# ESP8266.net
KiCad netlist of a schematic drawn in Altium Designer
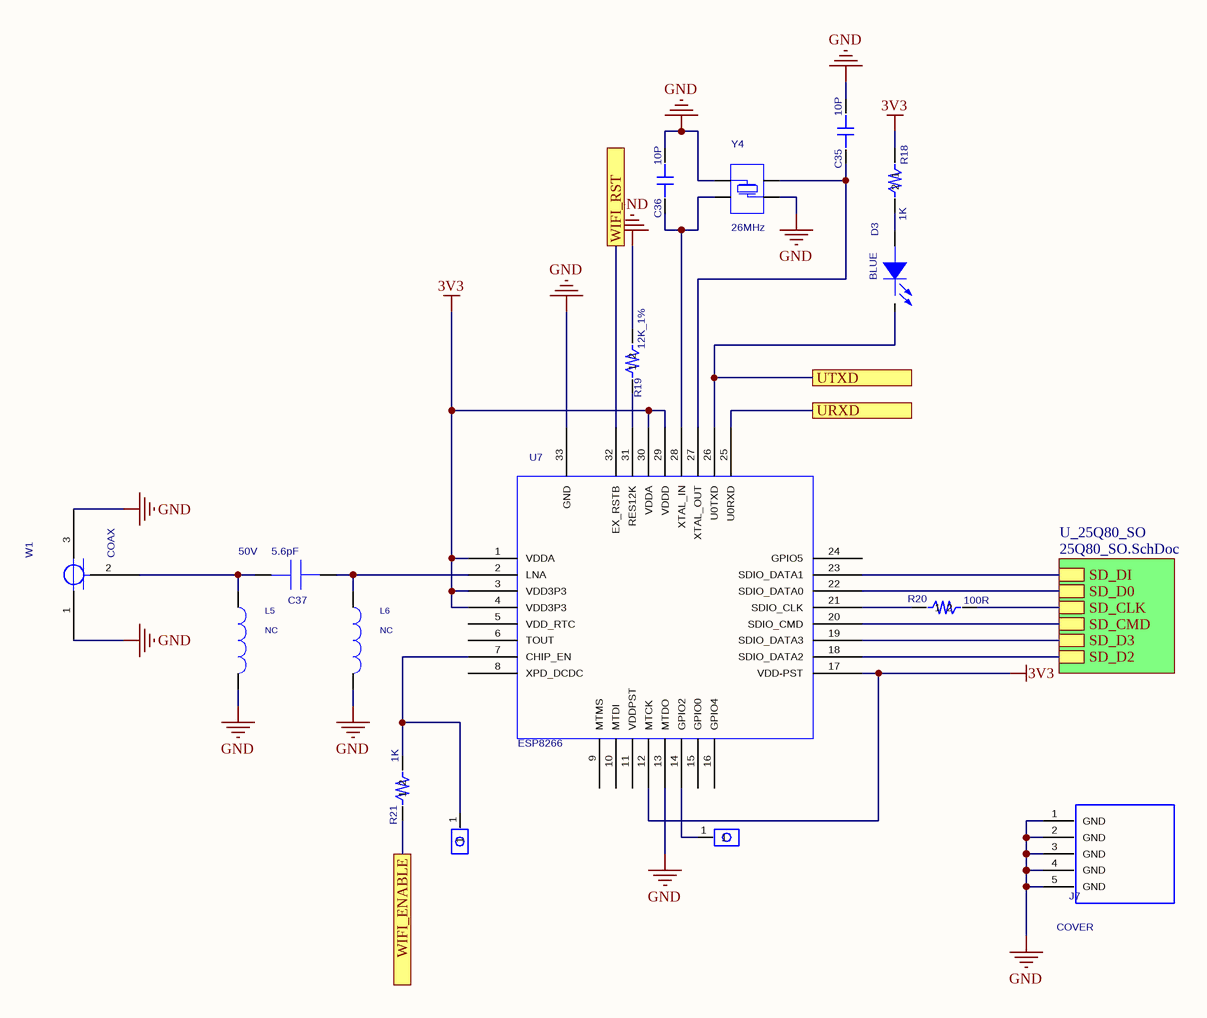
[diagram p0: ESP8266.SchDoc]

(export (version "E")
  (design (tool "Eeschema 10.0.6"))
  (components
    (comp (ref "C35")
      (value "10P")
      (footprint "RES_0603_FIRE")
      (description "0603")
      (fields (field (name "TOLERANCE") "+-5%") (field (name "Comment") "CAP_10P_0603_FIRE"))
      (libsource (lib "MINI-V3") (part "CAP_10P_0603_FIRE"))
    )
    (comp (ref "C36")
      (value "10P")
      (footprint "RES_0603_FIRE")
      (description "0603")
      (fields (field (name "TOLERANCE") "+-5%") (field (name "Comment") "CAP_10P_0603_FIRE"))
      (libsource (lib "MINI-V3") (part "CAP_10P_0603_FIRE"))
    )
    (comp (ref "C37")
      (value "5.6pF")
      (footprint "0603")
      (description "0603, X7R, 50V, 10%(K)")
      (fields (field (name "TOLERANCE") "±10%") (field (name "MFR") "Fenghua") (field (name "VOLTAGE") "50V"))
      (libsource (lib "MINI-V3") (part "CAP_NP"))
    )
    (comp (ref "D3")
      (value "BLUE")
      (footprint "LED_BLUE_0603_FIRE")
      (description "blue,0603")
      (fields (field (name "Comment") "LED_BLUE_0603_FIRE"))
      (libsource (lib "MINI-V3") (part "LED_BLUE_0603_FIRE"))
    )
    (comp (ref "J5") (value "1_DIP") (footprint "1_DIP") (libsource (lib "MINI-V3") (part "1_DIP")))
    (comp (ref "J6") (value "1_DIP") (footprint "1_DIP") (libsource (lib "MINI-V3") (part "1_DIP")))
    (comp (ref "J7") (value "COVER") (footprint "COVER1") (libsource (lib "MINI-V3") (part "COVER")))
    (comp (ref "L5")
      (value "NC")
      (footprint "0603")
      (description "1uH, 1.1R@245MHz, 245mA")
      (fields (field (name "TOLERANCE") "5%") (field (name "MFR") "TDK"))
      (libsource (lib "MINI-V3") (part "IND"))
    )
    (comp (ref "L6")
      (value "NC")
      (footprint "0603")
      (description "1uH, 1.1R@245MHz, 245mA")
      (fields (field (name "TOLERANCE") "5%") (field (name "MFR") "TDK"))
      (libsource (lib "MINI-V3") (part "IND"))
    )
    (comp (ref "R18")
      (value "1K")
      (footprint "RES_0603_FIRE")
      (description "0402")
      (fields (field (name "TOLERANCE") "+-5%") (field (name "Comment") "RES_1K_0603_FIRE"))
      (libsource (lib "MINI-V3") (part "RES_1K_0603_FIRE"))
    )
    (comp (ref "R19")
      (value "12K_1%")
      (footprint "RES_0603_FIRE")
      (description "0402")
      (fields (field (name "TOLERANCE") "+-1%") (field (name "Comment") "RES_12K_1%_0603_FIRE"))
      (libsource (lib "MINI-V3") (part "RES_12K_1%_0603_FIRE"))
    )
    (comp (ref "R20")
      (value "100R")
      (footprint "RES_0603_FIRE")
      (description "0402")
      (fields (field (name "TOLERANCE") "+-5%") (field (name "Comment") "RES_100R_0603_FIRE"))
      (libsource (lib "MINI-V3") (part "RES_100R_0603_FIRE"))
    )
    (comp (ref "R21")
      (value "1K")
      (footprint "RES_0603_FIRE")
      (description "0402")
      (fields (field (name "TOLERANCE") "+-5%") (field (name "Comment") "RES_1K_0603_FIRE"))
      (libsource (lib "MINI-V3") (part "RES_1K_0603_FIRE"))
    )
    (comp (ref "U7") (value "ESP8266") (footprint "QFN32_1") (libsource (lib "MINI-V3") (part "ESP8266")))
    (comp (ref "W1") (value "COAX") (footprint "UFL-3") (libsource (lib "MINI-V3") (part "COAX")))
    (comp (ref "Y4")
      (value "26MHz")
      (footprint "NX3225SA")
      (description "27.12MHz,SMD5032,-30 to 85℃")
      (fields (field (name "PART_NUMBER") "OS200008-01") (field (name "MFR_PART_NUMBER") "E5SB27_1200F20G13"))
      (libsource (lib "MINI-V3") (part "CRYSTAL5032"))
    )
  )
  (nets
    (net (code "1") (name "/SD_CLK") (class "Default")
      (node (ref "R20") (pin "2") (pinfunction "2_2") (pintype "passive"))
    )
    (net (code "2") (name "/SD_CMD") (class "Default")
      (node (ref "U7") (pin "20") (pinfunction "SDIO_CMD_20") (pintype "passive"))
    )
    (net (code "3") (name "/SD_D0") (class "Default")
      (node (ref "U7") (pin "22") (pinfunction "SDIO_DATA0_22") (pintype "passive"))
    )
    (net (code "4") (name "/SD_D2") (class "Default")
      (node (ref "U7") (pin "18") (pinfunction "SDIO_DATA2_18") (pintype "passive"))
    )
    (net (code "5") (name "/SD_D3") (class "Default")
      (node (ref "U7") (pin "19") (pinfunction "SDIO_DATA3_19") (pintype "passive"))
    )
    (net (code "6") (name "/SD_DI") (class "Default")
      (node (ref "U7") (pin "23") (pinfunction "SDIO_DATA1_23") (pintype "passive"))
    )
    (net (code "7") (name "/URXD") (class "Default")
      (node (ref "U7") (pin "25") (pinfunction "U0RXD_25") (pintype "passive"))
    )
    (net (code "8") (name "/UTXD") (class "Default")
      (node (ref "D3") (pin "K") (pinfunction "CATHODE_K") (pintype "passive"))
      (node (ref "U7") (pin "26") (pinfunction "U0TXD_26") (pintype "passive"))
    )
    (net (code "9") (name "/WIFI_ENABLE") (class "Default")
      (node (ref "R21") (pin "1") (pinfunction "1_1") (pintype "passive"))
    )
    (net (code "10") (name "/WIFI_RST") (class "Default")
      (node (ref "U7") (pin "32") (pinfunction "EX_RSTB_32") (pintype "passive"))
    )
    (net (code "11") (name "3V3") (class "Default")
      (node (ref "R18") (pin "1") (pinfunction "1_1") (pintype "passive"))
      (node (ref "U7") (pin "1") (pinfunction "VDDA_1") (pintype "passive"))
      (node (ref "U7") (pin "12") (pinfunction "MTCK_12") (pintype "passive"))
      (node (ref "U7") (pin "17") (pinfunction "VDD-PST_17") (pintype "passive"))
      (node (ref "U7") (pin "29") (pinfunction "VDDD_29") (pintype "passive"))
      (node (ref "U7") (pin "3") (pinfunction "VDD3P3_3") (pintype "passive"))
      (node (ref "U7") (pin "30") (pinfunction "VDDA_30") (pintype "passive"))
      (node (ref "U7") (pin "4") (pinfunction "VDD3P3_4") (pintype "passive"))
    )
    (net (code "12") (name "GND") (class "Default")
      (node (ref "C35") (pin "2") (pinfunction "2_2") (pintype "passive"))
      (node (ref "C36") (pin "2") (pinfunction "2_2") (pintype "passive"))
      (node (ref "J7") (pin "1") (pinfunction "GND_1") (pintype "passive"))
      (node (ref "J7") (pin "2") (pinfunction "GND_2") (pintype "passive"))
      (node (ref "J7") (pin "3") (pinfunction "GND_3") (pintype "passive"))
      (node (ref "J7") (pin "4") (pinfunction "GND_4") (pintype "passive"))
      (node (ref "J7") (pin "5") (pinfunction "GND_5") (pintype "passive"))
      (node (ref "L5") (pin "2") (pinfunction "2_2") (pintype "passive"))
      (node (ref "L6") (pin "2") (pinfunction "2_2") (pintype "passive"))
      (node (ref "R19") (pin "2") (pinfunction "2_2") (pintype "passive"))
      (node (ref "U7") (pin "13") (pinfunction "MTDO_13") (pintype "passive"))
      (node (ref "U7") (pin "33") (pinfunction "GND_33") (pintype "passive"))
      (node (ref "W1") (pin "1") (pinfunction "CENTER_1_1") (pintype "passive"))
      (node (ref "W1") (pin "3") (pinfunction "CENTER_2_3") (pintype "passive"))
      (node (ref "Y4") (pin "1") (pinfunction "1_1") (pintype "passive"))
      (node (ref "Y4") (pin "3") (pinfunction "3_3") (pintype "passive"))
    )
    (net (code "13") (name "Net-(D3-ANODE)") (class "Default")
      (node (ref "D3") (pin "A") (pinfunction "ANODE_A") (pintype "passive"))
      (node (ref "R18") (pin "2") (pinfunction "2_2") (pintype "passive"))
    )
    (net (code "14") (name "Net-(U7-CHIP_EN)") (class "Default")
      (node (ref "J6") (pin "1") (pinfunction "1_1") (pintype "passive"))
      (node (ref "R21") (pin "2") (pinfunction "2_2") (pintype "passive"))
      (node (ref "U7") (pin "7") (pinfunction "CHIP_EN_7") (pintype "passive"))
    )
    (net (code "15") (name "Net-(U7-GPIO2)") (class "Default")
      (node (ref "J5") (pin "1") (pinfunction "1_1") (pintype "passive"))
      (node (ref "U7") (pin "14") (pinfunction "GPIO2_14") (pintype "passive"))
    )
    (net (code "16") (name "Net-(U7-LNA)") (class "Default")
      (node (ref "C37") (pin "1") (pinfunction "1_1") (pintype "passive"))
      (node (ref "L6") (pin "1") (pinfunction "1_1") (pintype "passive"))
      (node (ref "U7") (pin "2") (pinfunction "LNA_2") (pintype "passive"))
    )
    (net (code "17") (name "Net-(U7-RES12K)") (class "Default")
      (node (ref "R19") (pin "1") (pinfunction "1_1") (pintype "passive"))
      (node (ref "U7") (pin "31") (pinfunction "RES12K_31") (pintype "passive"))
    )
    (net (code "18") (name "Net-(U7-SDIO_CLK)") (class "Default")
      (node (ref "R20") (pin "1") (pinfunction "1_1") (pintype "passive"))
      (node (ref "U7") (pin "21") (pinfunction "SDIO_CLK_21") (pintype "passive"))
    )
    (net (code "19") (name "Net-(U7-XTAL_IN)") (class "Default")
      (node (ref "C36") (pin "1") (pinfunction "1_1") (pintype "passive"))
      (node (ref "U7") (pin "28") (pinfunction "XTAL_IN_28") (pintype "passive"))
      (node (ref "Y4") (pin "2") (pinfunction "2_2") (pintype "passive"))
    )
    (net (code "20") (name "Net-(U7-XTAL_OUT)") (class "Default")
      (node (ref "C35") (pin "1") (pinfunction "1_1") (pintype "passive"))
      (node (ref "U7") (pin "27") (pinfunction "XTAL_OUT_27") (pintype "passive"))
      (node (ref "Y4") (pin "4") (pinfunction "4_4") (pintype "passive"))
    )
    (net (code "21") (name "Net-(W1-SHIELD)") (class "Default")
      (node (ref "C37") (pin "2") (pinfunction "2_2") (pintype "passive"))
      (node (ref "L5") (pin "1") (pinfunction "1_1") (pintype "passive"))
      (node (ref "W1") (pin "2") (pinfunction "SHIELD_2") (pintype "passive"))
    )
    (net (code "22") (name "unconnected-(U7-GPIO0-Pad15)") (class "Default")
      (node (ref "U7") (pin "15") (pinfunction "GPIO0_15") (pintype "passive"))
    )
    (net (code "23") (name "unconnected-(U7-GPIO4-Pad16)") (class "Default")
      (node (ref "U7") (pin "16") (pinfunction "GPIO4_16") (pintype "passive"))
    )
    (net (code "24") (name "unconnected-(U7-GPIO5-Pad24)") (class "Default")
      (node (ref "U7") (pin "24") (pinfunction "GPIO5_24") (pintype "passive"))
    )
    (net (code "25") (name "unconnected-(U7-MTDI-Pad10)") (class "Default")
      (node (ref "U7") (pin "10") (pinfunction "MTDI_10") (pintype "passive"))
    )
    (net (code "26") (name "unconnected-(U7-MTMS-Pad9)") (class "Default")
      (node (ref "U7") (pin "9") (pinfunction "MTMS_9") (pintype "passive"))
    )
    (net (code "27") (name "unconnected-(U7-TOUT-Pad6)") (class "Default")
      (node (ref "U7") (pin "6") (pinfunction "TOUT_6") (pintype "passive"))
    )
    (net (code "28") (name "unconnected-(U7-VDDPST-Pad11)") (class "Default")
      (node (ref "U7") (pin "11") (pinfunction "VDDPST_11") (pintype "passive"))
    )
    (net (code "29") (name "unconnected-(U7-VDD_RTC-Pad5)") (class "Default")
      (node (ref "U7") (pin "5") (pinfunction "VDD_RTC_5") (pintype "passive"))
    )
    (net (code "30") (name "unconnected-(U7-XPD_DCDC-Pad8)") (class "Default")
      (node (ref "U7") (pin "8") (pinfunction "XPD_DCDC_8") (pintype "passive"))
    )
  )
)
